# Mainboard.net
KiCad netlist of a schematic drawn in EAGLE
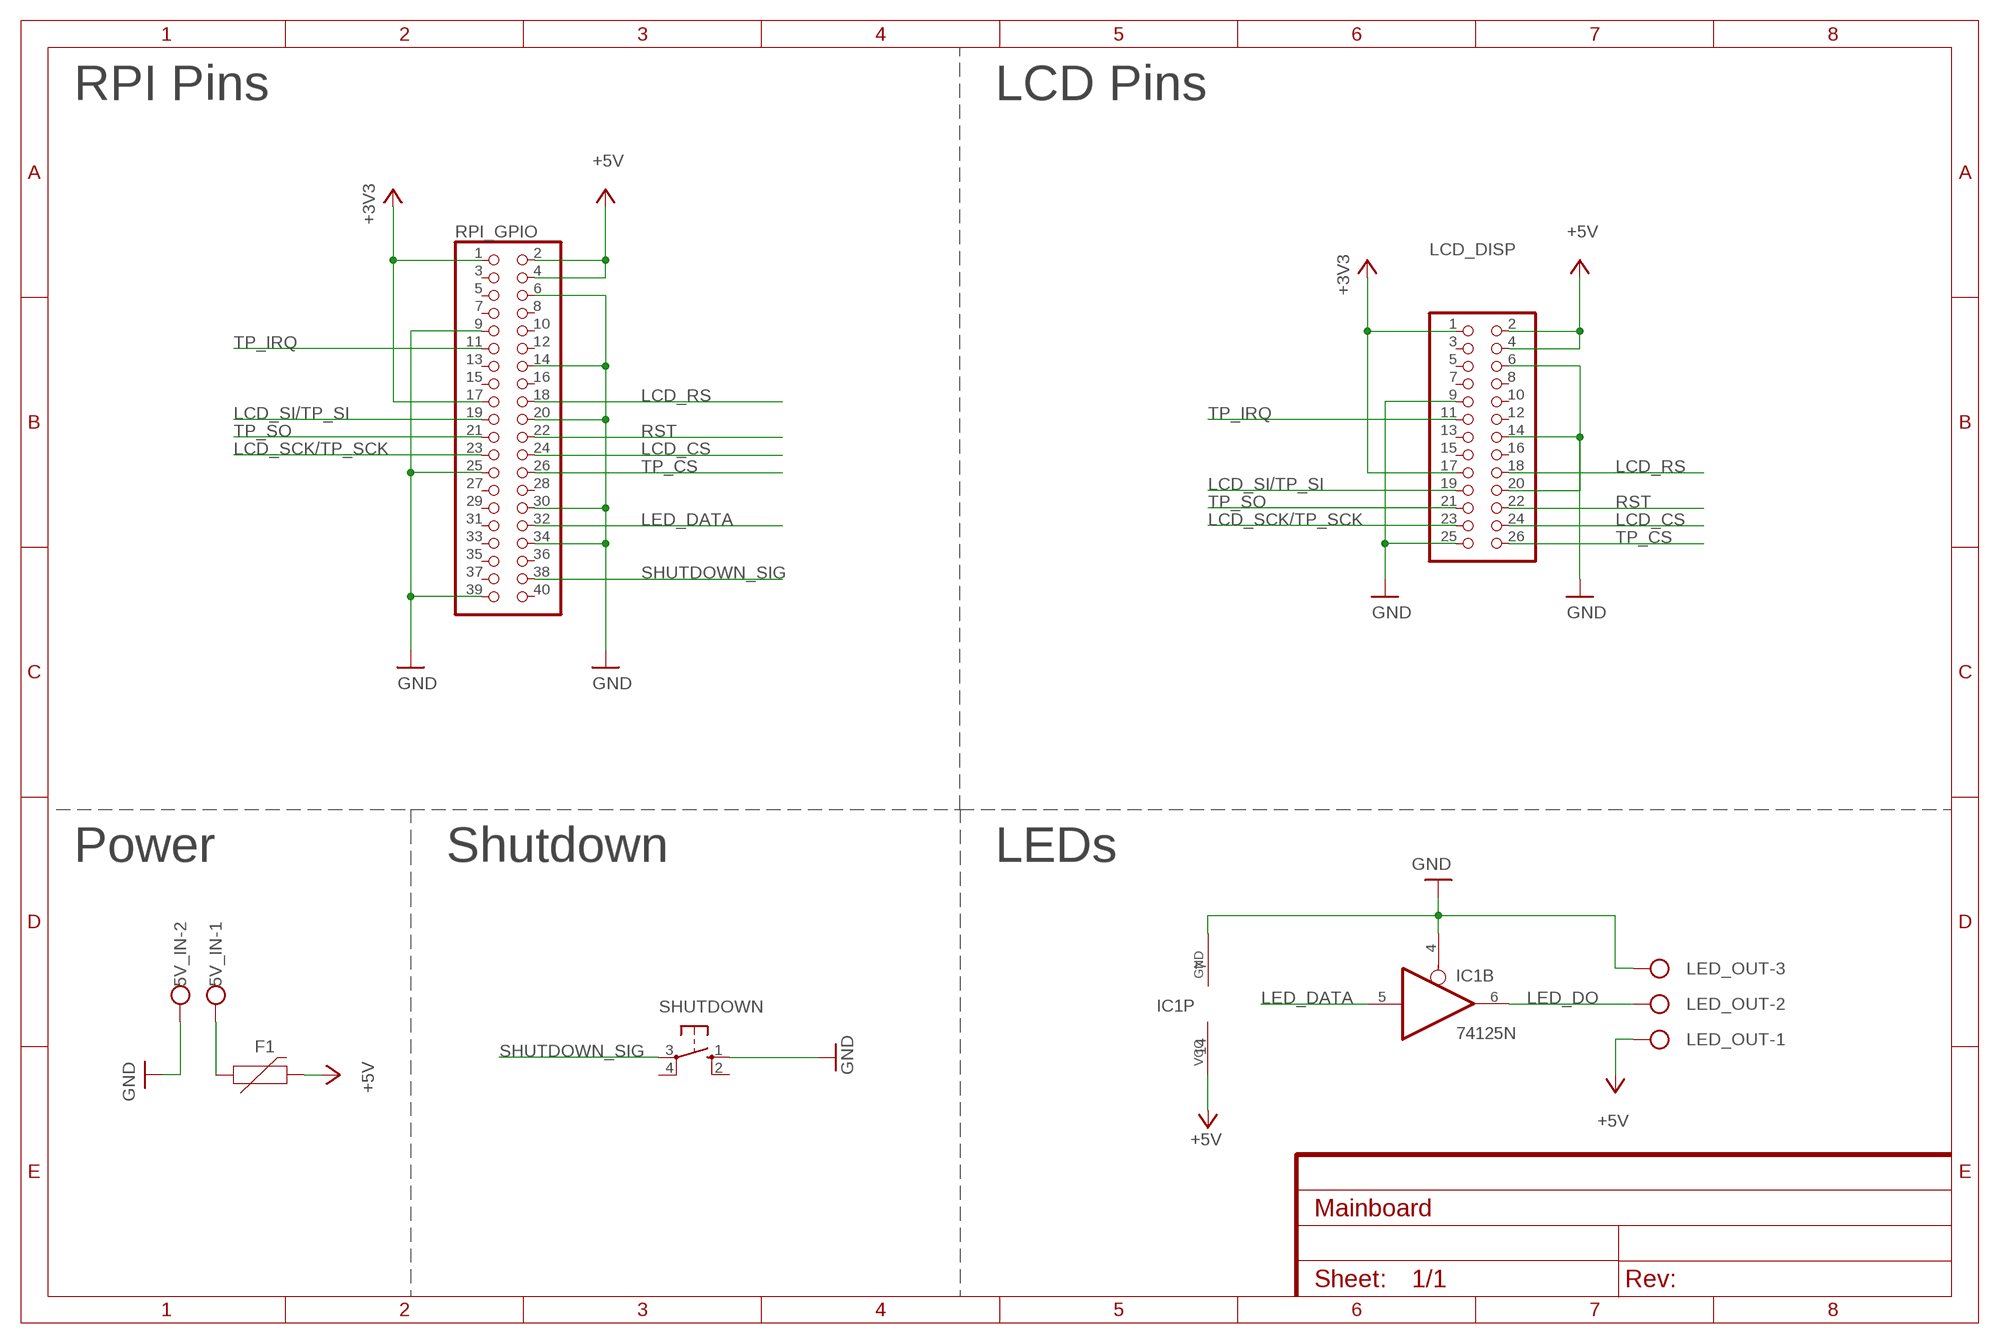
[diagram p0: schematic, sheet 1]

(export (version "E")
  (design (tool "Eeschema 10.0.6"))
  (components
    (comp (ref "5V_IN")
      (value "W237-102")
      (footprint "eagle-import:W237-102")
      (fields (field (name "MPN") "237-102"))
      (libsource (lib "eagle-import") (part "W237-102"))
    )
    (comp (ref "F1")
      (value "JK30-500")
      (footprint "eagle-import:JK30-500")
      (libsource (lib "eagle-import") (part "JK30-500"))
    )
    (comp (ref "IC1")
      (value "74125N")
      (footprint "eagle-import:DIL14")
      (libsource (lib "eagle-import") (part "74125N"))
    )
    (comp (ref "LCD_DISP")
      (value "PINHD-2X13")
      (footprint "eagle-import:2X13")
      (fields (field (name "SPICEPREFIX") "X"))
      (libsource (lib "eagle-import") (part "PINHD-2X13"))
    )
    (comp (ref "LED_OUT")
      (value "W237-103")
      (footprint "eagle-import:W237-103")
      (fields (field (name "MPN") "237-103"))
      (libsource (lib "eagle-import") (part "W237-103"))
    )
    (comp (ref "RPI_GPIO")
      (value "PINHD-2X20")
      (footprint "eagle-import:2X20")
      (libsource (lib "eagle-import") (part "PINHD-2X20"))
    )
    (comp (ref "SHUTDOWN")
      (value "40-XX")
      (footprint "eagle-import:B3F-40XX")
      (fields (field (name "MF") "OMRON COMPONENTS USA") (field (name "MPN") "B3F-4000"))
      (libsource (lib "eagle-import") (part "40-XX"))
    )
  )
  (nets
    (net (code "1") (name "+3V3") (class "Default")
      (node (ref "LCD_DISP") (pin "1") (pinfunction "1_1") (pintype "passive"))
      (node (ref "LCD_DISP") (pin "17") (pinfunction "17_17") (pintype "passive"))
      (node (ref "RPI_GPIO") (pin "1") (pinfunction "1_1") (pintype "passive"))
      (node (ref "RPI_GPIO") (pin "17") (pinfunction "17_17") (pintype "passive"))
    )
    (net (code "2") (name "+5V") (class "Default")
      (node (ref "F1") (pin "P$2") (pinfunction "2_P$2") (pintype "bidirectional"))
      (node (ref "IC1") (pin "14") (pinfunction "VCC_14") (pintype "power_in"))
      (node (ref "LCD_DISP") (pin "2") (pinfunction "2_2") (pintype "passive"))
      (node (ref "LCD_DISP") (pin "4") (pinfunction "4_4") (pintype "passive"))
      (node (ref "LED_OUT") (pin "1") (pinfunction "KL_1") (pintype "passive"))
      (node (ref "RPI_GPIO") (pin "2") (pinfunction "2_2") (pintype "passive"))
      (node (ref "RPI_GPIO") (pin "4") (pinfunction "4_4") (pintype "passive"))
    )
    (net (code "3") (name "/LCD_CS") (class "Default")
      (node (ref "LCD_DISP") (pin "24") (pinfunction "24_24") (pintype "passive"))
      (node (ref "RPI_GPIO") (pin "24") (pinfunction "24_24") (pintype "passive"))
    )
    (net (code "4") (name "/LCD_RS") (class "Default")
      (node (ref "LCD_DISP") (pin "18") (pinfunction "18_18") (pintype "passive"))
      (node (ref "RPI_GPIO") (pin "18") (pinfunction "18_18") (pintype "passive"))
    )
    (net (code "5") (name "/LCD_SCK{slash}TP_SCK") (class "Default")
      (node (ref "LCD_DISP") (pin "23") (pinfunction "23_23") (pintype "passive"))
      (node (ref "RPI_GPIO") (pin "23") (pinfunction "23_23") (pintype "passive"))
    )
    (net (code "6") (name "/LCD_SI{slash}TP_SI") (class "Default")
      (node (ref "LCD_DISP") (pin "19") (pinfunction "19_19") (pintype "passive"))
      (node (ref "RPI_GPIO") (pin "19") (pinfunction "19_19") (pintype "passive"))
    )
    (net (code "7") (name "/LED_DATA") (class "Default")
      (node (ref "IC1") (pin "5") (pinfunction "I_5") (pintype "input"))
      (node (ref "RPI_GPIO") (pin "32") (pinfunction "32_32") (pintype "passive"))
    )
    (net (code "8") (name "/LED_DO") (class "Default")
      (node (ref "IC1") (pin "6") (pinfunction "O_6") (pintype "tri_state"))
      (node (ref "LED_OUT") (pin "2") (pinfunction "KL_2") (pintype "passive"))
    )
    (net (code "9") (name "/RST") (class "Default")
      (node (ref "LCD_DISP") (pin "22") (pinfunction "22_22") (pintype "passive"))
      (node (ref "RPI_GPIO") (pin "22") (pinfunction "22_22") (pintype "passive"))
    )
    (net (code "10") (name "/SHUTDOWN_SIG") (class "Default")
      (node (ref "RPI_GPIO") (pin "38") (pinfunction "38_38") (pintype "passive"))
      (node (ref "SHUTDOWN") (pin "3") (pinfunction "P_3") (pintype "passive"))
    )
    (net (code "11") (name "/TP_CS") (class "Default")
      (node (ref "LCD_DISP") (pin "26") (pinfunction "26_26") (pintype "passive"))
      (node (ref "RPI_GPIO") (pin "26") (pinfunction "26_26") (pintype "passive"))
    )
    (net (code "12") (name "/TP_IRQ") (class "Default")
      (node (ref "LCD_DISP") (pin "11") (pinfunction "11_11") (pintype "passive"))
      (node (ref "RPI_GPIO") (pin "11") (pinfunction "11_11") (pintype "passive"))
    )
    (net (code "13") (name "/TP_SO") (class "Default")
      (node (ref "LCD_DISP") (pin "21") (pinfunction "21_21") (pintype "passive"))
      (node (ref "RPI_GPIO") (pin "21") (pinfunction "21_21") (pintype "passive"))
    )
    (net (code "14") (name "GND") (class "Default")
      (node (ref "5V_IN") (pin "2") (pinfunction "KL_2") (pintype "passive"))
      (node (ref "IC1") (pin "4") (pinfunction "OE_4") (pintype "input"))
      (node (ref "IC1") (pin "7") (pinfunction "GND_7") (pintype "power_in"))
      (node (ref "LCD_DISP") (pin "14") (pinfunction "14_14") (pintype "passive"))
      (node (ref "LCD_DISP") (pin "20") (pinfunction "20_20") (pintype "passive"))
      (node (ref "LCD_DISP") (pin "25") (pinfunction "25_25") (pintype "passive"))
      (node (ref "LCD_DISP") (pin "6") (pinfunction "6_6") (pintype "passive"))
      (node (ref "LCD_DISP") (pin "9") (pinfunction "9_9") (pintype "passive"))
      (node (ref "LED_OUT") (pin "3") (pinfunction "KL_3") (pintype "passive"))
      (node (ref "RPI_GPIO") (pin "14") (pinfunction "14_14") (pintype "passive"))
      (node (ref "RPI_GPIO") (pin "20") (pinfunction "20_20") (pintype "passive"))
      (node (ref "RPI_GPIO") (pin "25") (pinfunction "25_25") (pintype "passive"))
      (node (ref "RPI_GPIO") (pin "30") (pinfunction "30_30") (pintype "passive"))
      (node (ref "RPI_GPIO") (pin "34") (pinfunction "34_34") (pintype "passive"))
      (node (ref "RPI_GPIO") (pin "39") (pinfunction "39_39") (pintype "passive"))
      (node (ref "RPI_GPIO") (pin "6") (pinfunction "6_6") (pintype "passive"))
      (node (ref "RPI_GPIO") (pin "9") (pinfunction "9_9") (pintype "passive"))
      (node (ref "SHUTDOWN") (pin "1") (pinfunction "S_1") (pintype "passive"))
    )
    (net (code "15") (name "Net-(5V_INA-KL)") (class "Default")
      (node (ref "5V_IN") (pin "1") (pinfunction "KL_1") (pintype "passive"))
      (node (ref "F1") (pin "P$1") (pinfunction "1_P$1") (pintype "bidirectional"))
    )
    (net (code "16") (name "unconnected-(LCD_DISP-Pad3)") (class "Default")
      (node (ref "LCD_DISP") (pin "3") (pinfunction "3_3") (pintype "passive"))
    )
    (net (code "17") (name "unconnected-(LCD_DISP-Pad5)") (class "Default")
      (node (ref "LCD_DISP") (pin "5") (pinfunction "5_5") (pintype "passive"))
    )
    (net (code "18") (name "unconnected-(LCD_DISP-Pad7)") (class "Default")
      (node (ref "LCD_DISP") (pin "7") (pinfunction "7_7") (pintype "passive"))
    )
    (net (code "19") (name "unconnected-(LCD_DISP-Pad8)") (class "Default")
      (node (ref "LCD_DISP") (pin "8") (pinfunction "8_8") (pintype "passive"))
    )
    (net (code "20") (name "unconnected-(LCD_DISP-Pad10)") (class "Default")
      (node (ref "LCD_DISP") (pin "10") (pinfunction "10_10") (pintype "passive"))
    )
    (net (code "21") (name "unconnected-(LCD_DISP-Pad12)") (class "Default")
      (node (ref "LCD_DISP") (pin "12") (pinfunction "12_12") (pintype "passive"))
    )
    (net (code "22") (name "unconnected-(LCD_DISP-Pad13)") (class "Default")
      (node (ref "LCD_DISP") (pin "13") (pinfunction "13_13") (pintype "passive"))
    )
    (net (code "23") (name "unconnected-(LCD_DISP-Pad15)") (class "Default")
      (node (ref "LCD_DISP") (pin "15") (pinfunction "15_15") (pintype "passive"))
    )
    (net (code "24") (name "unconnected-(LCD_DISP-Pad16)") (class "Default")
      (node (ref "LCD_DISP") (pin "16") (pinfunction "16_16") (pintype "passive"))
    )
    (net (code "25") (name "unconnected-(RPI_GPIO-Pad3)") (class "Default")
      (node (ref "RPI_GPIO") (pin "3") (pinfunction "3_3") (pintype "passive"))
    )
    (net (code "26") (name "unconnected-(RPI_GPIO-Pad5)") (class "Default")
      (node (ref "RPI_GPIO") (pin "5") (pinfunction "5_5") (pintype "passive"))
    )
    (net (code "27") (name "unconnected-(RPI_GPIO-Pad7)") (class "Default")
      (node (ref "RPI_GPIO") (pin "7") (pinfunction "7_7") (pintype "passive"))
    )
    (net (code "28") (name "unconnected-(RPI_GPIO-Pad8)") (class "Default")
      (node (ref "RPI_GPIO") (pin "8") (pinfunction "8_8") (pintype "passive"))
    )
    (net (code "29") (name "unconnected-(RPI_GPIO-Pad10)") (class "Default")
      (node (ref "RPI_GPIO") (pin "10") (pinfunction "10_10") (pintype "passive"))
    )
    (net (code "30") (name "unconnected-(RPI_GPIO-Pad12)") (class "Default")
      (node (ref "RPI_GPIO") (pin "12") (pinfunction "12_12") (pintype "passive"))
    )
    (net (code "31") (name "unconnected-(RPI_GPIO-Pad13)") (class "Default")
      (node (ref "RPI_GPIO") (pin "13") (pinfunction "13_13") (pintype "passive"))
    )
    (net (code "32") (name "unconnected-(RPI_GPIO-Pad15)") (class "Default")
      (node (ref "RPI_GPIO") (pin "15") (pinfunction "15_15") (pintype "passive"))
    )
    (net (code "33") (name "unconnected-(RPI_GPIO-Pad16)") (class "Default")
      (node (ref "RPI_GPIO") (pin "16") (pinfunction "16_16") (pintype "passive"))
    )
    (net (code "34") (name "unconnected-(RPI_GPIO-Pad27)") (class "Default")
      (node (ref "RPI_GPIO") (pin "27") (pinfunction "27_27") (pintype "passive"))
    )
    (net (code "35") (name "unconnected-(RPI_GPIO-Pad28)") (class "Default")
      (node (ref "RPI_GPIO") (pin "28") (pinfunction "28_28") (pintype "passive"))
    )
    (net (code "36") (name "unconnected-(RPI_GPIO-Pad29)") (class "Default")
      (node (ref "RPI_GPIO") (pin "29") (pinfunction "29_29") (pintype "passive"))
    )
    (net (code "37") (name "unconnected-(RPI_GPIO-Pad31)") (class "Default")
      (node (ref "RPI_GPIO") (pin "31") (pinfunction "31_31") (pintype "passive"))
    )
    (net (code "38") (name "unconnected-(RPI_GPIO-Pad33)") (class "Default")
      (node (ref "RPI_GPIO") (pin "33") (pinfunction "33_33") (pintype "passive"))
    )
    (net (code "39") (name "unconnected-(RPI_GPIO-Pad35)") (class "Default")
      (node (ref "RPI_GPIO") (pin "35") (pinfunction "35_35") (pintype "passive"))
    )
    (net (code "40") (name "unconnected-(RPI_GPIO-Pad36)") (class "Default")
      (node (ref "RPI_GPIO") (pin "36") (pinfunction "36_36") (pintype "passive"))
    )
    (net (code "41") (name "unconnected-(RPI_GPIO-Pad37)") (class "Default")
      (node (ref "RPI_GPIO") (pin "37") (pinfunction "37_37") (pintype "passive"))
    )
    (net (code "42") (name "unconnected-(RPI_GPIO-Pad40)") (class "Default")
      (node (ref "RPI_GPIO") (pin "40") (pinfunction "40_40") (pintype "passive"))
    )
    (net (code "43") (name "unconnected-(SHUTDOWN-P1-Pad4)") (class "Default")
      (node (ref "SHUTDOWN") (pin "4") (pinfunction "P1_4") (pintype "passive"))
    )
    (net (code "44") (name "unconnected-(SHUTDOWN-S1-Pad2)") (class "Default")
      (node (ref "SHUTDOWN") (pin "2") (pinfunction "S1_2") (pintype "passive"))
    )
  )
)
